# sensors-v2.net
KiCad netlist of a schematic drawn in EAGLE
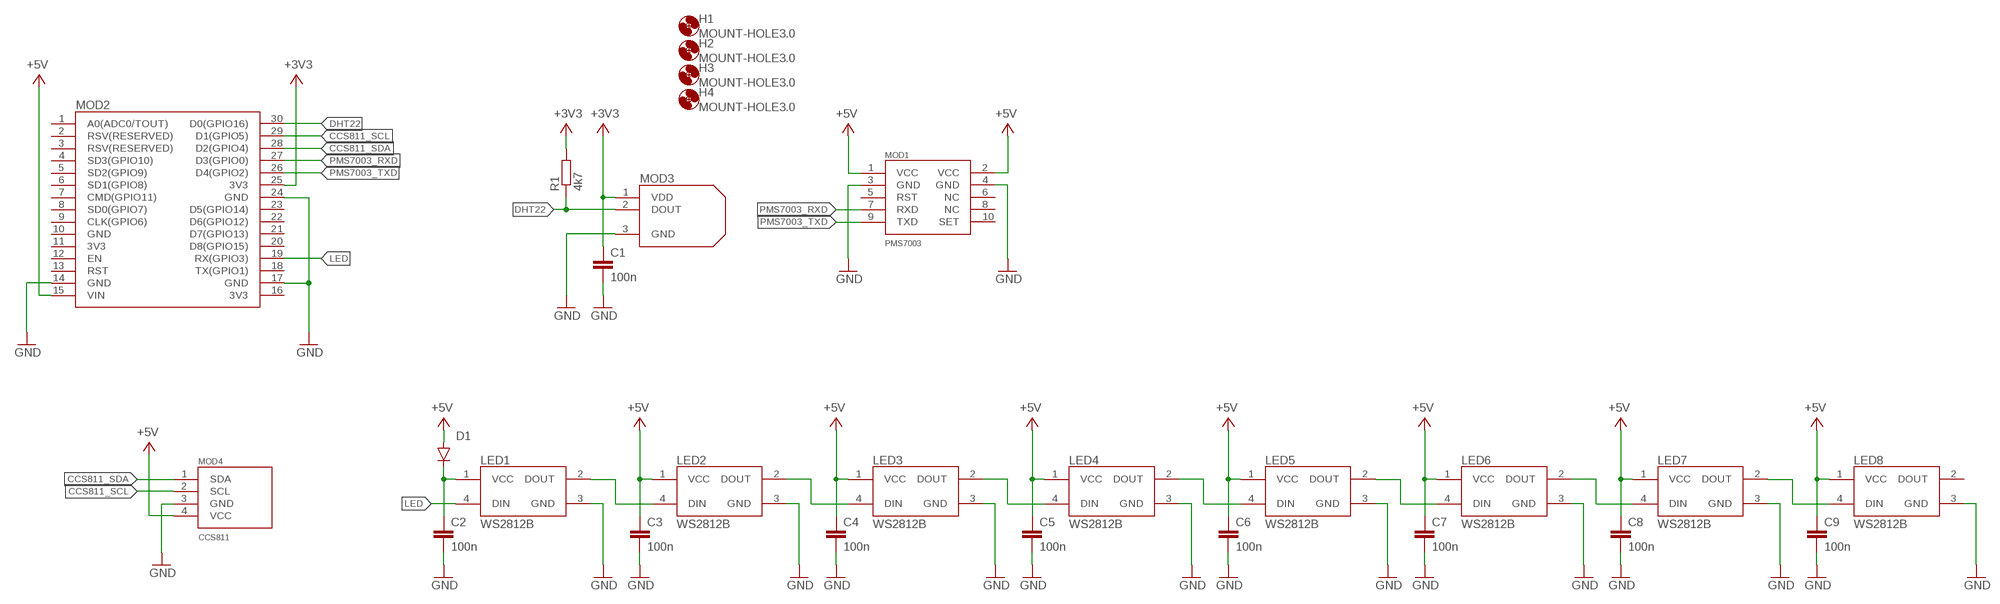
[diagram p0: schematic, sheet 1]

(export (version "E")
  (design (tool "Eeschema 10.0.6"))
  (components
    (comp (ref "C1")
      (value "100n")
      (footprint "eagle-import:C0603")
      (libsource (lib "eagle-import") (part "C-EUC0603"))
    )
    (comp (ref "C2")
      (value "100n")
      (footprint "eagle-import:C0603")
      (libsource (lib "eagle-import") (part "C-EUC0603"))
    )
    (comp (ref "C3")
      (value "100n")
      (footprint "eagle-import:C0603")
      (libsource (lib "eagle-import") (part "C-EUC0603"))
    )
    (comp (ref "C4")
      (value "100n")
      (footprint "eagle-import:C0603")
      (libsource (lib "eagle-import") (part "C-EUC0603"))
    )
    (comp (ref "C5")
      (value "100n")
      (footprint "eagle-import:C0603")
      (libsource (lib "eagle-import") (part "C-EUC0603"))
    )
    (comp (ref "C6")
      (value "100n")
      (footprint "eagle-import:C0603")
      (libsource (lib "eagle-import") (part "C-EUC0603"))
    )
    (comp (ref "C7")
      (value "100n")
      (footprint "eagle-import:C0603")
      (libsource (lib "eagle-import") (part "C-EUC0603"))
    )
    (comp (ref "C8")
      (value "100n")
      (footprint "eagle-import:C0603")
      (libsource (lib "eagle-import") (part "C-EUC0603"))
    )
    (comp (ref "C9")
      (value "100n")
      (footprint "eagle-import:C0603")
      (libsource (lib "eagle-import") (part "C-EUC0603"))
    )
    (comp (ref "D1")
      (value "DIODE-MINIMELF")
      (footprint "eagle-import:MINIMELF")
      (libsource (lib "eagle-import") (part "DIODE-MINIMELF"))
    )
    (comp (ref "H1")
      (value "MOUNT-HOLE3.0")
      (footprint "eagle-import:3,0")
      (libsource (lib "eagle-import") (part "MOUNT-HOLE3.0"))
    )
    (comp (ref "H2")
      (value "MOUNT-HOLE3.0")
      (footprint "eagle-import:3,0")
      (libsource (lib "eagle-import") (part "MOUNT-HOLE3.0"))
    )
    (comp (ref "H3")
      (value "MOUNT-HOLE3.0")
      (footprint "eagle-import:3,0")
      (libsource (lib "eagle-import") (part "MOUNT-HOLE3.0"))
    )
    (comp (ref "H4")
      (value "MOUNT-HOLE3.0")
      (footprint "eagle-import:3,0")
      (libsource (lib "eagle-import") (part "MOUNT-HOLE3.0"))
    )
    (comp (ref "LED1")
      (value "WS2812B")
      (footprint "eagle-import:WS2812B")
      (libsource (lib "eagle-import") (part "WS2812B"))
    )
    (comp (ref "LED2")
      (value "WS2812B")
      (footprint "eagle-import:WS2812B")
      (libsource (lib "eagle-import") (part "WS2812B"))
    )
    (comp (ref "LED3")
      (value "WS2812B")
      (footprint "eagle-import:WS2812B")
      (libsource (lib "eagle-import") (part "WS2812B"))
    )
    (comp (ref "LED4")
      (value "WS2812B")
      (footprint "eagle-import:WS2812B")
      (libsource (lib "eagle-import") (part "WS2812B"))
    )
    (comp (ref "LED5")
      (value "WS2812B")
      (footprint "eagle-import:WS2812B")
      (libsource (lib "eagle-import") (part "WS2812B"))
    )
    (comp (ref "LED6")
      (value "WS2812B")
      (footprint "eagle-import:WS2812B")
      (libsource (lib "eagle-import") (part "WS2812B"))
    )
    (comp (ref "LED7")
      (value "WS2812B")
      (footprint "eagle-import:WS2812B")
      (libsource (lib "eagle-import") (part "WS2812B"))
    )
    (comp (ref "LED8")
      (value "WS2812B")
      (footprint "eagle-import:WS2812B")
      (libsource (lib "eagle-import") (part "WS2812B"))
    )
    (comp (ref "MOD1")
      (value "PMS7003")
      (footprint "eagle-import:PMS7003")
      (libsource (lib "eagle-import") (part "PMS7003"))
    )
    (comp (ref "MOD2")
      (value "NODEMCU")
      (footprint "eagle-import:NODEMCU-WITHOUT-HOLES")
      (libsource (lib "eagle-import") (part "NODEMCUWITHOUT-HOLES"))
    )
    (comp (ref "MOD3")
      (value "DHT22")
      (footprint "eagle-import:DHT22_STRAIGHT-3PIN")
      (libsource (lib "eagle-import") (part "DHT22-3PIN"))
    )
    (comp (ref "MOD4")
      (value "CCS811")
      (footprint "eagle-import:HDRRAR4W64P254_1X4_1016X736X254B")
      (libsource (lib "eagle-import") (part "CCS811_ANGLE"))
    )
    (comp (ref "R1")
      (value "4k7")
      (footprint "eagle-import:M0805")
      (libsource (lib "eagle-import") (part "R-EU_M0805"))
    )
  )
  (nets
    (net (code "1") (name "+3V3") (class "Default")
      (node (ref "C1") (pin "1") (pinfunction "1_1") (pintype "passive"))
      (node (ref "MOD2") (pin "25") (pinfunction "3V3_25") (pintype "bidirectional"))
      (node (ref "MOD3") (pin "1") (pinfunction "VDD_1") (pintype "bidirectional"))
      (node (ref "R1") (pin "2") (pinfunction "2_2") (pintype "passive"))
    )
    (net (code "2") (name "+5V") (class "Default")
      (node (ref "C3") (pin "1") (pinfunction "1_1") (pintype "passive"))
      (node (ref "C4") (pin "1") (pinfunction "1_1") (pintype "passive"))
      (node (ref "C5") (pin "1") (pinfunction "1_1") (pintype "passive"))
      (node (ref "C6") (pin "1") (pinfunction "1_1") (pintype "passive"))
      (node (ref "C7") (pin "1") (pinfunction "1_1") (pintype "passive"))
      (node (ref "C8") (pin "1") (pinfunction "1_1") (pintype "passive"))
      (node (ref "C9") (pin "1") (pinfunction "1_1") (pintype "passive"))
      (node (ref "D1") (pin "A") (pinfunction "A_A") (pintype "passive"))
      (node (ref "LED2") (pin "1") (pinfunction "VCC_1") (pintype "bidirectional"))
      (node (ref "LED3") (pin "1") (pinfunction "VCC_1") (pintype "bidirectional"))
      (node (ref "LED4") (pin "1") (pinfunction "VCC_1") (pintype "bidirectional"))
      (node (ref "LED5") (pin "1") (pinfunction "VCC_1") (pintype "bidirectional"))
      (node (ref "LED6") (pin "1") (pinfunction "VCC_1") (pintype "bidirectional"))
      (node (ref "LED7") (pin "1") (pinfunction "VCC_1") (pintype "bidirectional"))
      (node (ref "LED8") (pin "1") (pinfunction "VCC_1") (pintype "bidirectional"))
      (node (ref "MOD1") (pin "1") (pinfunction "VCC_1") (pintype "bidirectional"))
      (node (ref "MOD1") (pin "2") (pinfunction "VCC_2") (pintype "bidirectional"))
      (node (ref "MOD2") (pin "15") (pinfunction "VIN_15") (pintype "bidirectional"))
      (node (ref "MOD4") (pin "4") (pinfunction "VCC_4") (pintype "bidirectional"))
    )
    (net (code "3") (name "CCS811_SCL") (class "Default")
      (node (ref "MOD2") (pin "29") (pinfunction "D1(GPIO5)_29") (pintype "bidirectional"))
      (node (ref "MOD4") (pin "2") (pinfunction "SCL_2") (pintype "bidirectional"))
    )
    (net (code "4") (name "CCS811_SDA") (class "Default")
      (node (ref "MOD2") (pin "28") (pinfunction "D2(GPIO4)_28") (pintype "bidirectional"))
      (node (ref "MOD4") (pin "1") (pinfunction "SDA_1") (pintype "bidirectional"))
    )
    (net (code "5") (name "DHT22") (class "Default")
      (node (ref "MOD2") (pin "30") (pinfunction "D0(GPIO16)_30") (pintype "bidirectional"))
      (node (ref "MOD3") (pin "2") (pinfunction "DOUT_2") (pintype "bidirectional"))
      (node (ref "R1") (pin "1") (pinfunction "1_1") (pintype "passive"))
    )
    (net (code "6") (name "GND") (class "Default")
      (node (ref "C1") (pin "2") (pinfunction "2_2") (pintype "passive"))
      (node (ref "C2") (pin "2") (pinfunction "2_2") (pintype "passive"))
      (node (ref "C3") (pin "2") (pinfunction "2_2") (pintype "passive"))
      (node (ref "C4") (pin "2") (pinfunction "2_2") (pintype "passive"))
      (node (ref "C5") (pin "2") (pinfunction "2_2") (pintype "passive"))
      (node (ref "C6") (pin "2") (pinfunction "2_2") (pintype "passive"))
      (node (ref "C7") (pin "2") (pinfunction "2_2") (pintype "passive"))
      (node (ref "C8") (pin "2") (pinfunction "2_2") (pintype "passive"))
      (node (ref "C9") (pin "2") (pinfunction "2_2") (pintype "passive"))
      (node (ref "LED1") (pin "3") (pinfunction "GND_3") (pintype "bidirectional"))
      (node (ref "LED2") (pin "3") (pinfunction "GND_3") (pintype "bidirectional"))
      (node (ref "LED3") (pin "3") (pinfunction "GND_3") (pintype "bidirectional"))
      (node (ref "LED4") (pin "3") (pinfunction "GND_3") (pintype "bidirectional"))
      (node (ref "LED5") (pin "3") (pinfunction "GND_3") (pintype "bidirectional"))
      (node (ref "LED6") (pin "3") (pinfunction "GND_3") (pintype "bidirectional"))
      (node (ref "LED7") (pin "3") (pinfunction "GND_3") (pintype "bidirectional"))
      (node (ref "LED8") (pin "3") (pinfunction "GND_3") (pintype "bidirectional"))
      (node (ref "MOD1") (pin "3") (pinfunction "GND_3") (pintype "bidirectional"))
      (node (ref "MOD1") (pin "4") (pinfunction "GND_4") (pintype "bidirectional"))
      (node (ref "MOD2") (pin "14") (pinfunction "GND_14") (pintype "bidirectional"))
      (node (ref "MOD2") (pin "17") (pinfunction "GND_17") (pintype "bidirectional"))
      (node (ref "MOD2") (pin "24") (pinfunction "GND_24") (pintype "bidirectional"))
      (node (ref "MOD3") (pin "3") (pinfunction "GND_3") (pintype "bidirectional"))
      (node (ref "MOD4") (pin "3") (pinfunction "GND_3") (pintype "bidirectional"))
    )
    (net (code "7") (name "LED") (class "Default")
      (node (ref "LED1") (pin "4") (pinfunction "DIN_4") (pintype "bidirectional"))
      (node (ref "MOD2") (pin "19") (pinfunction "RX(GPIO3)_19") (pintype "bidirectional"))
    )
    (net (code "8") (name "Net-(LED1-DOUT)") (class "Default")
      (node (ref "LED1") (pin "2") (pinfunction "DOUT_2") (pintype "bidirectional"))
      (node (ref "LED2") (pin "4") (pinfunction "DIN_4") (pintype "bidirectional"))
    )
    (net (code "9") (name "Net-(LED1-VCC)") (class "Default")
      (node (ref "C2") (pin "1") (pinfunction "1_1") (pintype "passive"))
      (node (ref "D1") (pin "C") (pinfunction "C_C") (pintype "passive"))
      (node (ref "LED1") (pin "1") (pinfunction "VCC_1") (pintype "bidirectional"))
    )
    (net (code "10") (name "Net-(LED2-DOUT)") (class "Default")
      (node (ref "LED2") (pin "2") (pinfunction "DOUT_2") (pintype "bidirectional"))
      (node (ref "LED3") (pin "4") (pinfunction "DIN_4") (pintype "bidirectional"))
    )
    (net (code "11") (name "Net-(LED3-DOUT)") (class "Default")
      (node (ref "LED3") (pin "2") (pinfunction "DOUT_2") (pintype "bidirectional"))
      (node (ref "LED4") (pin "4") (pinfunction "DIN_4") (pintype "bidirectional"))
    )
    (net (code "12") (name "Net-(LED4-DOUT)") (class "Default")
      (node (ref "LED4") (pin "2") (pinfunction "DOUT_2") (pintype "bidirectional"))
      (node (ref "LED5") (pin "4") (pinfunction "DIN_4") (pintype "bidirectional"))
    )
    (net (code "13") (name "Net-(LED5-DOUT)") (class "Default")
      (node (ref "LED5") (pin "2") (pinfunction "DOUT_2") (pintype "bidirectional"))
      (node (ref "LED6") (pin "4") (pinfunction "DIN_4") (pintype "bidirectional"))
    )
    (net (code "14") (name "Net-(LED6-DOUT)") (class "Default")
      (node (ref "LED6") (pin "2") (pinfunction "DOUT_2") (pintype "bidirectional"))
      (node (ref "LED7") (pin "4") (pinfunction "DIN_4") (pintype "bidirectional"))
    )
    (net (code "15") (name "Net-(LED7-DOUT)") (class "Default")
      (node (ref "LED7") (pin "2") (pinfunction "DOUT_2") (pintype "bidirectional"))
      (node (ref "LED8") (pin "4") (pinfunction "DIN_4") (pintype "bidirectional"))
    )
    (net (code "16") (name "PMS7003_RXD") (class "Default")
      (node (ref "MOD1") (pin "7") (pinfunction "RXD_7") (pintype "bidirectional"))
      (node (ref "MOD2") (pin "27") (pinfunction "D3(GPIO0)_27") (pintype "bidirectional"))
    )
    (net (code "17") (name "PMS7003_TXD") (class "Default")
      (node (ref "MOD1") (pin "9") (pinfunction "TXD_9") (pintype "bidirectional"))
      (node (ref "MOD2") (pin "26") (pinfunction "D4(GPIO2)_26") (pintype "bidirectional"))
    )
    (net (code "18") (name "unconnected-(LED8-DOUT-Pad2)") (class "Default")
      (node (ref "LED8") (pin "2") (pinfunction "DOUT_2") (pintype "bidirectional"))
    )
    (net (code "19") (name "unconnected-(MOD1-NC-Pad6)") (class "Default")
      (node (ref "MOD1") (pin "6") (pinfunction "NC_6") (pintype "bidirectional"))
    )
    (net (code "20") (name "unconnected-(MOD1-NC-Pad8)") (class "Default")
      (node (ref "MOD1") (pin "8") (pinfunction "NC_8") (pintype "bidirectional"))
    )
    (net (code "21") (name "unconnected-(MOD1-RST-Pad5)") (class "Default")
      (node (ref "MOD1") (pin "5") (pinfunction "RST_5") (pintype "bidirectional"))
    )
    (net (code "22") (name "unconnected-(MOD1-SET-Pad10)") (class "Default")
      (node (ref "MOD1") (pin "10") (pinfunction "SET_10") (pintype "bidirectional"))
    )
    (net (code "23") (name "unconnected-(MOD2-3V3-Pad11)") (class "Default")
      (node (ref "MOD2") (pin "11") (pinfunction "3V3_11") (pintype "bidirectional"))
    )
    (net (code "24") (name "unconnected-(MOD2-3V3-Pad16)") (class "Default")
      (node (ref "MOD2") (pin "16") (pinfunction "3V3_16") (pintype "bidirectional"))
    )
    (net (code "25") (name "unconnected-(MOD2-A0(ADC0{slash}TOUT)-Pad1)") (class "Default")
      (node (ref "MOD2") (pin "1") (pinfunction "A0(ADC0/TOUT)_1") (pintype "bidirectional"))
    )
    (net (code "26") (name "unconnected-(MOD2-CLK(GPIO6)-Pad9)") (class "Default")
      (node (ref "MOD2") (pin "9") (pinfunction "CLK(GPIO6)_9") (pintype "bidirectional"))
    )
    (net (code "27") (name "unconnected-(MOD2-CMD(GPIO11)-Pad7)") (class "Default")
      (node (ref "MOD2") (pin "7") (pinfunction "CMD(GPIO11)_7") (pintype "bidirectional"))
    )
    (net (code "28") (name "unconnected-(MOD2-D5(GPIO14)-Pad23)") (class "Default")
      (node (ref "MOD2") (pin "23") (pinfunction "D5(GPIO14)_23") (pintype "bidirectional"))
    )
    (net (code "29") (name "unconnected-(MOD2-D6(GPIO12)-Pad22)") (class "Default")
      (node (ref "MOD2") (pin "22") (pinfunction "D6(GPIO12)_22") (pintype "bidirectional"))
    )
    (net (code "30") (name "unconnected-(MOD2-D7(GPIO13)-Pad21)") (class "Default")
      (node (ref "MOD2") (pin "21") (pinfunction "D7(GPIO13)_21") (pintype "bidirectional"))
    )
    (net (code "31") (name "unconnected-(MOD2-D8(GPIO15)-Pad20)") (class "Default")
      (node (ref "MOD2") (pin "20") (pinfunction "D8(GPIO15)_20") (pintype "bidirectional"))
    )
    (net (code "32") (name "unconnected-(MOD2-EN-Pad12)") (class "Default")
      (node (ref "MOD2") (pin "12") (pinfunction "EN_12") (pintype "bidirectional"))
    )
    (net (code "33") (name "unconnected-(MOD2-GND-Pad10)") (class "Default")
      (node (ref "MOD2") (pin "10") (pinfunction "GND_10") (pintype "bidirectional"))
    )
    (net (code "34") (name "unconnected-(MOD2-RST-Pad13)") (class "Default")
      (node (ref "MOD2") (pin "13") (pinfunction "RST_13") (pintype "bidirectional"))
    )
    (net (code "35") (name "unconnected-(MOD2-RSV(RESERVED)-Pad2)") (class "Default")
      (node (ref "MOD2") (pin "2") (pinfunction "RSV(RESERVED)_2") (pintype "bidirectional"))
    )
    (net (code "36") (name "unconnected-(MOD2-RSV(RESERVED)-Pad3)") (class "Default")
      (node (ref "MOD2") (pin "3") (pinfunction "RSV(RESERVED)_3") (pintype "bidirectional"))
    )
    (net (code "37") (name "unconnected-(MOD2-SD0(GPIO7)-Pad8)") (class "Default")
      (node (ref "MOD2") (pin "8") (pinfunction "SD0(GPIO7)_8") (pintype "bidirectional"))
    )
    (net (code "38") (name "unconnected-(MOD2-SD1(GPIO8)-Pad6)") (class "Default")
      (node (ref "MOD2") (pin "6") (pinfunction "SD1(GPIO8)_6") (pintype "bidirectional"))
    )
    (net (code "39") (name "unconnected-(MOD2-SD2(GPIO9)-Pad5)") (class "Default")
      (node (ref "MOD2") (pin "5") (pinfunction "SD2(GPIO9)_5") (pintype "bidirectional"))
    )
    (net (code "40") (name "unconnected-(MOD2-SD3(GPIO10)-Pad4)") (class "Default")
      (node (ref "MOD2") (pin "4") (pinfunction "SD3(GPIO10)_4") (pintype "bidirectional"))
    )
    (net (code "41") (name "unconnected-(MOD2-TX(GPIO1)-Pad18)") (class "Default")
      (node (ref "MOD2") (pin "18") (pinfunction "TX(GPIO1)_18") (pintype "bidirectional"))
    )
  )
)
